# design.net
KiCad netlist of a schematic drawn in Altium Designer
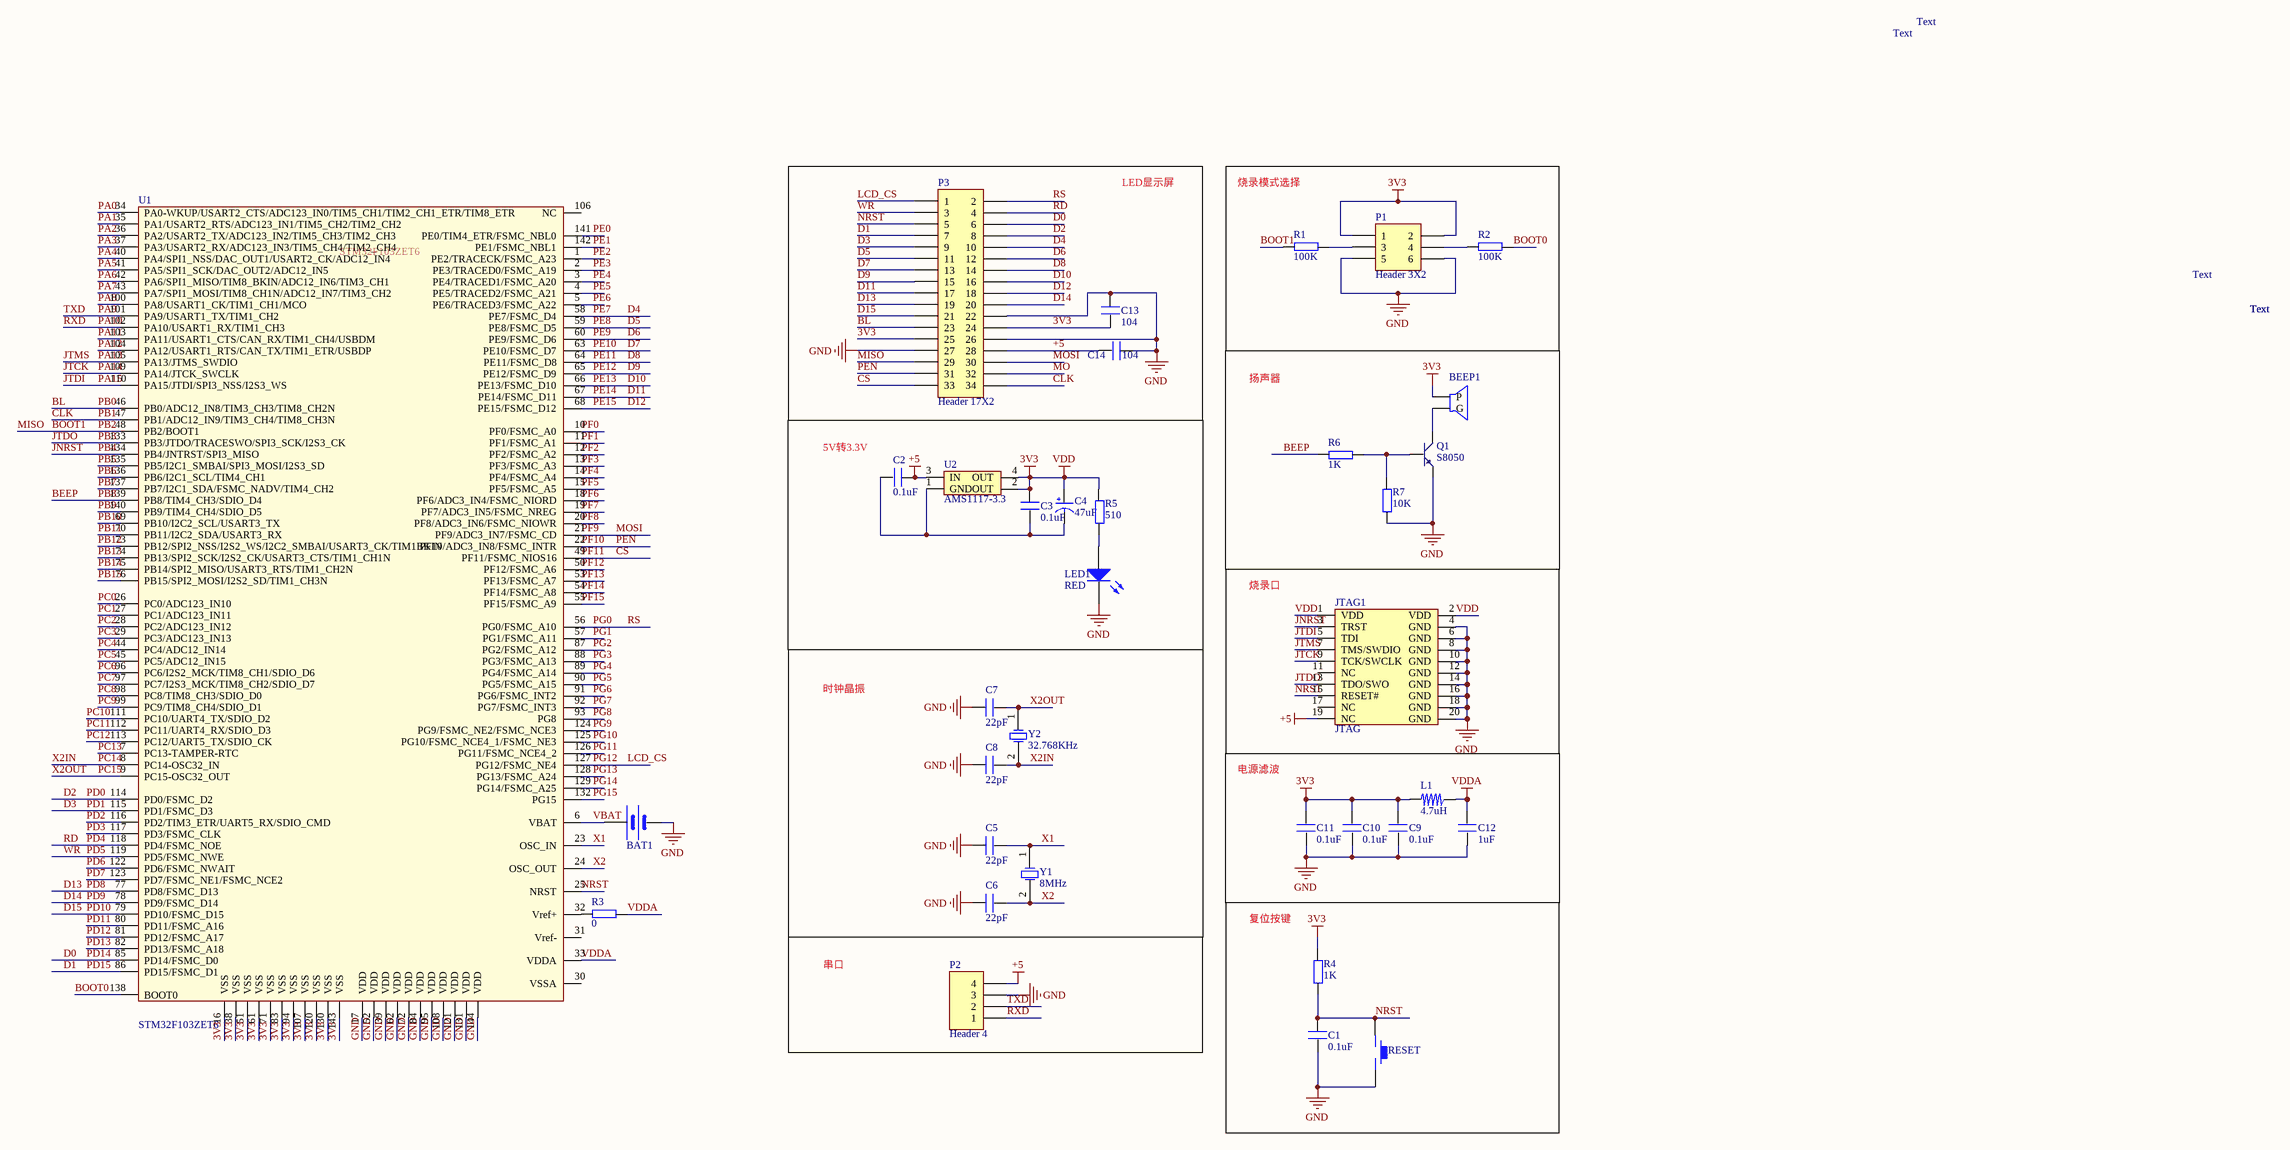
[diagram p0: 新苗.SchDoc]

(export (version "E")
  (design (tool "Eeschema 10.0.6"))
  (components
    (comp (ref "BAT1")
      (value "BATT")
      (footprint "BATM")
      (libsource (lib "WarShip V3 STM32103封装库") (part "BAT"))
    )
    (comp (ref "BEEP1")
      (value "BEEP")
      (footprint "BELL-5")
      (libsource (lib "WarShip V3 STM32103封装库") (part "BEEP"))
    )
    (comp (ref "C1")
      (value "0.1uF")
      (footprint "0603P")
      (libsource (lib "WarShip V3 STM32103封装库") (part "C"))
    )
    (comp (ref "C2")
      (value "0.1uF")
      (footprint "0603P")
      (libsource (lib "WarShip V3 STM32103封装库") (part "C"))
    )
    (comp (ref "C3")
      (value "0.1uF")
      (footprint "0603P")
      (libsource (lib "WarShip V3 STM32103封装库") (part "C"))
    )
    (comp (ref "C4")
      (value "47uF")
      (footprint "CC6.56.5")
      (libsource (lib "WarShip V3 STM32103封装库") (part "CAP"))
    )
    (comp (ref "C5") (value "22pF") (footprint "0603P") (libsource (lib "WarShip V3 STM32103封装库") (part "C")))
    (comp (ref "C6") (value "22pF") (footprint "0603P") (libsource (lib "WarShip V3 STM32103封装库") (part "C")))
    (comp (ref "C7") (value "22pF") (footprint "0603P") (libsource (lib "WarShip V3 STM32103封装库") (part "C")))
    (comp (ref "C8") (value "22pF") (footprint "0603P") (libsource (lib "WarShip V3 STM32103封装库") (part "C")))
    (comp (ref "C9")
      (value "0.1uF")
      (footprint "0603P")
      (libsource (lib "WarShip V3 STM32103封装库") (part "C"))
    )
    (comp (ref "C10")
      (value "0.1uF")
      (footprint "0603P")
      (libsource (lib "WarShip V3 STM32103封装库") (part "C"))
    )
    (comp (ref "C11")
      (value "0.1uF")
      (footprint "0603P")
      (libsource (lib "WarShip V3 STM32103封装库") (part "C"))
    )
    (comp (ref "C12") (value "1uF") (footprint "0603P") (libsource (lib "WarShip V3 STM32103封装库") (part "C")))
    (comp (ref "C13") (value "104") (footprint "0603P") (libsource (lib "WarShip V3 STM32103封装库") (part "C")))
    (comp (ref "C14") (value "104") (footprint "0603P") (libsource (lib "WarShip V3 STM32103封装库") (part "C")))
    (comp (ref "JTAG1")
      (value "JTAG")
      (footprint "JTAG_20")
      (libsource (lib "WarShip V3 STM32103封装库") (part "JTAG"))
    )
    (comp (ref "L1")
      (value "4.7uH")
      (footprint "L_SOP74")
      (libsource (lib "WarShip V3 STM32103封装库") (part "L_SOP"))
    )
    (comp (ref "LED1")
      (value "RED")
      (footprint "SMDLED")
      (description "Typical RED, GREEN, YELLOW, AMBER GaAs LED")
      (fields (field (name "PUBLISHER") "Altium Limited"))
      (libsource (lib "WarShip V3 STM32103封装库") (part "LED2"))
    )
    (comp (ref "P1")
      (value "Header 3X2")
      (footprint "HDR2X3")
      (description "Header, 3-Pin, Dual row")
      (fields (field (name "PUBLISHER") "Altium Limited"))
      (libsource (lib "Miscellaneous Connectors") (part "Header 3X2"))
    )
    (comp (ref "P2")
      (value "Header 4")
      (footprint "HDR1X4")
      (description "Header, 4-Pin")
      (fields (field (name "PUBLISHER") "Altium Limited"))
      (libsource (lib "WarShip V3 STM32103封装库") (part "Header 4"))
    )
    (comp (ref "P3")
      (value "Header 17X2")
      (footprint "HDR2X17")
      (description "Header, 17-Pin, Dual row")
      (fields (field (name "PUBLISHER") "Altium Limited"))
      (libsource (lib "Miscellaneous Connectors") (part "Header 17X2"))
    )
    (comp (ref "Q1")
      (value "S8050")
      (footprint "SOT-23R")
      (description "8050/BCW846/BCW847")
      (libsource (lib "WarShip V3 STM32103封装库") (part "NPN"))
    )
    (comp (ref "R1") (value "100K") (footprint "0603P") (libsource (lib "WarShip V3 STM32103封装库") (part "R")))
    (comp (ref "R2") (value "100K") (footprint "0603P") (libsource (lib "WarShip V3 STM32103封装库") (part "R")))
    (comp (ref "R3") (value "0") (footprint "0603P") (libsource (lib "WarShip V3 STM32103封装库") (part "R")))
    (comp (ref "R4") (value "1K") (footprint "0603P") (libsource (lib "WarShip V3 STM32103封装库") (part "R")))
    (comp (ref "R5") (value "510") (footprint "0603P") (libsource (lib "WarShip V3 STM32103封装库") (part "R")))
    (comp (ref "R6") (value "1K") (footprint "0603P") (libsource (lib "WarShip V3 STM32103封装库") (part "R")))
    (comp (ref "R7") (value "10K") (footprint "0603P") (libsource (lib "WarShip V3 STM32103封装库") (part "R")))
    (comp (ref "RESET")
      (value "KEY_M")
      (footprint "KEY_M")
      (libsource (lib "WarShip V3 STM32103封装库") (part "KEY_M"))
    )
    (comp (ref "U1")
      (value "STM32F103ZET6")
      (footprint "LQFP144")
      (libsource (lib "WarShip V3 STM32103封装库") (part "STM32F103ZET6"))
    )
    (comp (ref "U2")
      (value "AMS1117-3.3")
      (footprint "AMS1117")
      (libsource (lib "WarShip V3 STM32103封装库") (part "AMS1117"))
    )
    (comp (ref "Y1")
      (value "8MHz")
      (footprint "XTAL_US")
      (description "Crystal Oscillator")
      (fields (field (name "PUBLISHER") "Altium Limited"))
      (libsource (lib "WarShip V3 STM32103封装库") (part "XTAL"))
    )
    (comp (ref "Y2")
      (value "32.768KHz")
      (footprint "XTAL_US")
      (description "Crystal Oscillator")
      (fields (field (name "PUBLISHER") "Altium Limited"))
      (libsource (lib "WarShip V3 STM32103封装库") (part "XTAL"))
    )
  )
  (nets
    (net (code "1") (name "+5") (class "Default")
      (node (ref "C14") (pin "2") (pintype "passive"))
      (node (ref "C2") (pin "1") (pintype "passive"))
      (node (ref "JTAG1") (pin "19") (pinfunction "NC_19") (pintype "passive"))
      (node (ref "P2") (pin "4") (pinfunction "4_4") (pintype "passive"))
      (node (ref "P3") (pin "28") (pinfunction "28_28") (pintype "passive"))
      (node (ref "U2") (pin "3") (pinfunction "IN_3") (pintype "passive"))
    )
    (net (code "2") (name "/BEEP") (class "Default")
      (node (ref "R6") (pin "1") (pintype "passive"))
      (node (ref "U1") (pin "139") (pinfunction "PB8/TIM4_CH3/SDIO_D4_139") (pintype "passive"))
    )
    (net (code "3") (name "/BL") (class "Default")
      (node (ref "P3") (pin "23") (pinfunction "23_23") (pintype "passive"))
      (node (ref "U1") (pin "46") (pinfunction "PB0/ADC12_IN8/TIM3_CH3/TIM8_CH2N_46") (pintype "passive"))
    )
    (net (code "4") (name "/BOOT0") (class "Default")
      (node (ref "R2") (pin "1") (pintype "passive"))
      (node (ref "U1") (pin "138") (pinfunction "BOOT0_138") (pintype "passive"))
    )
    (net (code "5") (name "/BOOT1") (class "Default")
      (node (ref "P3") (pin "29") (pinfunction "29_29") (pintype "passive"))
      (node (ref "R1") (pin "2") (pintype "passive"))
      (node (ref "U1") (pin "48") (pinfunction "PB2/BOOT1_48") (pintype "passive"))
    )
    (net (code "6") (name "/CLK") (class "Default")
      (node (ref "P3") (pin "34") (pinfunction "34_34") (pintype "passive"))
      (node (ref "U1") (pin "47") (pinfunction "PB1/ADC12_IN9/TIM3_CH4/TIM8_CH3N_47") (pintype "passive"))
    )
    (net (code "7") (name "/CS") (class "Default")
      (node (ref "P3") (pin "33") (pinfunction "33_33") (pintype "passive"))
      (node (ref "U1") (pin "49") (pinfunction "PF11/FSMC_NIOS16_49") (pintype "passive"))
    )
    (net (code "8") (name "/D0") (class "Default")
      (node (ref "P3") (pin "6") (pinfunction "6_6") (pintype "passive"))
      (node (ref "U1") (pin "85") (pinfunction "PD14/FSMC_D0_85") (pintype "passive"))
    )
    (net (code "9") (name "/D1") (class "Default")
      (node (ref "P3") (pin "7") (pinfunction "7_7") (pintype "passive"))
      (node (ref "U1") (pin "86") (pinfunction "PD15/FSMC_D1_86") (pintype "passive"))
    )
    (net (code "10") (name "/D2") (class "Default")
      (node (ref "P3") (pin "8") (pinfunction "8_8") (pintype "passive"))
      (node (ref "U1") (pin "114") (pinfunction "PD0/FSMC_D2_114") (pintype "passive"))
    )
    (net (code "11") (name "/D3") (class "Default")
      (node (ref "P3") (pin "9") (pinfunction "9_9") (pintype "passive"))
      (node (ref "U1") (pin "115") (pinfunction "PD1/FSMC_D3_115") (pintype "passive"))
    )
    (net (code "12") (name "/D4") (class "Default")
      (node (ref "P3") (pin "10") (pinfunction "10_10") (pintype "passive"))
      (node (ref "U1") (pin "58") (pinfunction "PE7/FSMC_D4_58") (pintype "passive"))
    )
    (net (code "13") (name "/D5") (class "Default")
      (node (ref "P3") (pin "11") (pinfunction "11_11") (pintype "passive"))
      (node (ref "U1") (pin "59") (pinfunction "PE8/FSMC_D5_59") (pintype "passive"))
    )
    (net (code "14") (name "/D6") (class "Default")
      (node (ref "P3") (pin "12") (pinfunction "12_12") (pintype "passive"))
      (node (ref "U1") (pin "60") (pinfunction "PE9/FSMC_D6_60") (pintype "passive"))
    )
    (net (code "15") (name "/D7") (class "Default")
      (node (ref "P3") (pin "13") (pinfunction "13_13") (pintype "passive"))
      (node (ref "U1") (pin "63") (pinfunction "PE10/FSMC_D7_63") (pintype "passive"))
    )
    (net (code "16") (name "/D8") (class "Default")
      (node (ref "P3") (pin "14") (pinfunction "14_14") (pintype "passive"))
      (node (ref "U1") (pin "64") (pinfunction "PE11/FSMC_D8_64") (pintype "passive"))
    )
    (net (code "17") (name "/D9") (class "Default")
      (node (ref "P3") (pin "15") (pinfunction "15_15") (pintype "passive"))
      (node (ref "U1") (pin "65") (pinfunction "PE12/FSMC_D9_65") (pintype "passive"))
    )
    (net (code "18") (name "/D10") (class "Default")
      (node (ref "P3") (pin "16") (pinfunction "16_16") (pintype "passive"))
      (node (ref "U1") (pin "66") (pinfunction "PE13/FSMC_D10_66") (pintype "passive"))
    )
    (net (code "19") (name "/D11") (class "Default")
      (node (ref "P3") (pin "17") (pinfunction "17_17") (pintype "passive"))
      (node (ref "U1") (pin "67") (pinfunction "PE14/FSMC_D11_67") (pintype "passive"))
    )
    (net (code "20") (name "/D12") (class "Default")
      (node (ref "P3") (pin "18") (pinfunction "18_18") (pintype "passive"))
      (node (ref "U1") (pin "68") (pinfunction "PE15/FSMC_D12_68") (pintype "passive"))
    )
    (net (code "21") (name "/D13") (class "Default")
      (node (ref "P3") (pin "19") (pinfunction "19_19") (pintype "passive"))
      (node (ref "U1") (pin "77") (pinfunction "PD8/FSMC_D13_77") (pintype "passive"))
    )
    (net (code "22") (name "/D14") (class "Default")
      (node (ref "P3") (pin "20") (pinfunction "20_20") (pintype "passive"))
      (node (ref "U1") (pin "78") (pinfunction "PD9/FSMC_D14_78") (pintype "passive"))
    )
    (net (code "23") (name "/D15") (class "Default")
      (node (ref "P3") (pin "21") (pinfunction "21_21") (pintype "passive"))
      (node (ref "U1") (pin "79") (pinfunction "PD10/FSMC_D15_79") (pintype "passive"))
    )
    (net (code "24") (name "/JNRST") (class "Default")
      (node (ref "JTAG1") (pin "3") (pinfunction "TRST_3") (pintype "passive"))
      (node (ref "U1") (pin "134") (pinfunction "PB4/JNTRST/SPI3_MISO_134") (pintype "passive"))
    )
    (net (code "25") (name "/JTCK") (class "Default")
      (node (ref "JTAG1") (pin "9") (pinfunction "TCK/SWCLK_9") (pintype "passive"))
      (node (ref "U1") (pin "109") (pinfunction "PA14/JTCK_SWCLK_109") (pintype "passive"))
    )
    (net (code "26") (name "/JTDI") (class "Default")
      (node (ref "JTAG1") (pin "5") (pinfunction "TDI_5") (pintype "passive"))
      (node (ref "U1") (pin "110") (pinfunction "PA15/JTDI/SPI3_NSS/I2S3_WS_110") (pintype "passive"))
    )
    (net (code "27") (name "/JTDO") (class "Default")
      (node (ref "JTAG1") (pin "13") (pinfunction "TDO/SWO_13") (pintype "passive"))
      (node (ref "U1") (pin "133") (pinfunction "PB3/JTDO/TRACESWO/SPI3_SCK/I2S3_CK_133") (pintype "passive"))
    )
    (net (code "28") (name "/JTMS") (class "Default")
      (node (ref "JTAG1") (pin "7") (pinfunction "TMS/SWDIO_7") (pintype "passive"))
      (node (ref "U1") (pin "105") (pinfunction "PA13/JTMS_SWDIO_105") (pintype "passive"))
    )
    (net (code "29") (name "/LCD_CS") (class "Default")
      (node (ref "P3") (pin "1") (pinfunction "1_1") (pintype "passive"))
      (node (ref "U1") (pin "127") (pinfunction "PG12/FSMC_NE4_127") (pintype "passive"))
    )
    (net (code "30") (name "/MO") (class "Default")
      (node (ref "P3") (pin "32") (pinfunction "32_32") (pintype "passive"))
    )
    (net (code "31") (name "/MOSI") (class "Default")
      (node (ref "P3") (pin "30") (pinfunction "30_30") (pintype "passive"))
      (node (ref "U1") (pin "21") (pinfunction "PF9/ADC3_IN7/FSMC_CD_21") (pintype "passive"))
    )
    (net (code "32") (name "/NRST") (class "Default")
      (node (ref "C1") (pin "2") (pintype "passive"))
      (node (ref "JTAG1") (pin "15") (pinfunction "RESET#_15") (pintype "passive"))
      (node (ref "P3") (pin "5") (pinfunction "5_5") (pintype "passive"))
      (node (ref "R4") (pin "1") (pintype "passive"))
      (node (ref "RESET") (pin "1") (pinfunction "1_1") (pintype "passive"))
      (node (ref "U1") (pin "25") (pinfunction "NRST_25") (pintype "passive"))
    )
    (net (code "33") (name "/PA0") (class "Default")
      (node (ref "U1") (pin "34") (pinfunction "PA0-WKUP/USART2_CTS/ADC123_IN0/TIM5_CH1/TIM2_CH1_ETR/TIM8_ETR_34") (pintype "passive"))
    )
    (net (code "34") (name "/PA1") (class "Default")
      (node (ref "U1") (pin "35") (pinfunction "PA1/USART2_RTS/ADC123_IN1/TIM5_CH2/TIM2_CH2_35") (pintype "passive"))
    )
    (net (code "35") (name "/PA2") (class "Default")
      (node (ref "U1") (pin "36") (pinfunction "PA2/USART2_TX/ADC123_IN2/TIM5_CH3/TIM2_CH3_36") (pintype "passive"))
    )
    (net (code "36") (name "/PA3") (class "Default")
      (node (ref "U1") (pin "37") (pinfunction "PA3/USART2_RX/ADC123_IN3/TIM5_CH4/TIM2_CH4_37") (pintype "passive"))
    )
    (net (code "37") (name "/PA4") (class "Default")
      (node (ref "U1") (pin "40") (pinfunction "PA4/SPI1_NSS/DAC_OUT1/USART2_CK/ADC12_IN4_40") (pintype "passive"))
    )
    (net (code "38") (name "/PA5") (class "Default")
      (node (ref "U1") (pin "41") (pinfunction "PA5/SPI1_SCK/DAC_OUT2/ADC12_IN5_41") (pintype "passive"))
    )
    (net (code "39") (name "/PA6") (class "Default")
      (node (ref "U1") (pin "42") (pinfunction "PA6/SPI1_MISO/TIM8_BKIN/ADC12_IN6/TIM3_CH1_42") (pintype "passive"))
    )
    (net (code "40") (name "/PA7") (class "Default")
      (node (ref "U1") (pin "43") (pinfunction "PA7/SPI1_MOSI/TIM8_CH1N/ADC12_IN7/TIM3_CH2_43") (pintype "passive"))
    )
    (net (code "41") (name "/PA8") (class "Default")
      (node (ref "U1") (pin "100") (pinfunction "PA8/USART1_CK/TIM1_CH1/MCO_100") (pintype "passive"))
    )
    (net (code "42") (name "/PA9") (class "Default")
      (node (ref "P2") (pin "2") (pinfunction "2_2") (pintype "passive"))
      (node (ref "U1") (pin "101") (pinfunction "PA9/USART1_TX/TIM1_CH2_101") (pintype "passive"))
    )
    (net (code "43") (name "/PA10") (class "Default")
      (node (ref "P2") (pin "1") (pinfunction "1_1") (pintype "passive"))
      (node (ref "U1") (pin "102") (pinfunction "PA10/USART1_RX/TIM1_CH3_102") (pintype "passive"))
    )
    (net (code "44") (name "/PA11") (class "Default")
      (node (ref "U1") (pin "103") (pinfunction "PA11/USART1_CTS/CAN_RX/TIM1_CH4/USBDM_103") (pintype "passive"))
    )
    (net (code "45") (name "/PA12") (class "Default")
      (node (ref "U1") (pin "104") (pinfunction "PA12/USART1_RTS/CAN_TX/TIM1_ETR/USBDP_104") (pintype "passive"))
    )
    (net (code "46") (name "/PB5") (class "Default")
      (node (ref "U1") (pin "135") (pinfunction "PB5/I2C1_SMBAI/SPI3_MOSI/I2S3_SD_135") (pintype "passive"))
    )
    (net (code "47") (name "/PB6") (class "Default")
      (node (ref "U1") (pin "136") (pinfunction "PB6/I2C1_SCL/TIM4_CH1_136") (pintype "passive"))
    )
    (net (code "48") (name "/PB7") (class "Default")
      (node (ref "U1") (pin "137") (pinfunction "PB7/I2C1_SDA/FSMC_NADV/TIM4_CH2_137") (pintype "passive"))
    )
    (net (code "49") (name "/PB9") (class "Default")
      (node (ref "U1") (pin "140") (pinfunction "PB9/TIM4_CH4/SDIO_D5_140") (pintype "passive"))
    )
    (net (code "50") (name "/PB10") (class "Default")
      (node (ref "U1") (pin "69") (pinfunction "PB10/I2C2_SCL/USART3_TX_69") (pintype "passive"))
    )
    (net (code "51") (name "/PB11") (class "Default")
      (node (ref "U1") (pin "70") (pinfunction "PB11/I2C2_SDA/USART3_RX_70") (pintype "passive"))
    )
    (net (code "52") (name "/PB12") (class "Default")
      (node (ref "U1") (pin "73") (pinfunction "PB12/SPI2_NSS/I2S2_WS/I2C2_SMBAI/USART3_CK/TIM1BKIN_73") (pintype "passive"))
    )
    (net (code "53") (name "/PB13") (class "Default")
      (node (ref "U1") (pin "74") (pinfunction "PB13/SPI2_SCK/I2S2_CK/USART3_CTS/TIM1_CH1N_74") (pintype "passive"))
    )
    (net (code "54") (name "/PB14") (class "Default")
      (node (ref "U1") (pin "75") (pinfunction "PB14/SPI2_MISO/USART3_RTS/TIM1_CH2N_75") (pintype "passive"))
    )
    (net (code "55") (name "/PB15") (class "Default")
      (node (ref "U1") (pin "76") (pinfunction "PB15/SPI2_MOSI/I2S2_SD/TIM1_CH3N_76") (pintype "passive"))
    )
    (net (code "56") (name "/PC0") (class "Default")
      (node (ref "U1") (pin "26") (pinfunction "PC0/ADC123_IN10_26") (pintype "passive"))
    )
    (net (code "57") (name "/PC1") (class "Default")
      (node (ref "U1") (pin "27") (pinfunction "PC1/ADC123_IN11_27") (pintype "passive"))
    )
    (net (code "58") (name "/PC2") (class "Default")
      (node (ref "U1") (pin "28") (pinfunction "PC2/ADC123_IN12_28") (pintype "passive"))
    )
    (net (code "59") (name "/PC3") (class "Default")
      (node (ref "U1") (pin "29") (pinfunction "PC3/ADC123_IN13_29") (pintype "passive"))
    )
    (net (code "60") (name "/PC4") (class "Default")
      (node (ref "U1") (pin "44") (pinfunction "PC4/ADC12_IN14_44") (pintype "passive"))
    )
    (net (code "61") (name "/PC5") (class "Default")
      (node (ref "U1") (pin "45") (pinfunction "PC5/ADC12_IN15_45") (pintype "passive"))
    )
    (net (code "62") (name "/PC6") (class "Default")
      (node (ref "U1") (pin "96") (pinfunction "PC6/I2S2_MCK/TIM8_CH1/SDIO_D6_96") (pintype "passive"))
    )
    (net (code "63") (name "/PC7") (class "Default")
      (node (ref "U1") (pin "97") (pinfunction "PC7/I2S3_MCK/TIM8_CH2/SDIO_D7_97") (pintype "passive"))
    )
    (net (code "64") (name "/PC8") (class "Default")
      (node (ref "U1") (pin "98") (pinfunction "PC8/TIM8_CH3/SDIO_D0_98") (pintype "passive"))
    )
    (net (code "65") (name "/PC9") (class "Default")
      (node (ref "U1") (pin "99") (pinfunction "PC9/TIM8_CH4/SDIO_D1_99") (pintype "passive"))
    )
    (net (code "66") (name "/PC10") (class "Default")
      (node (ref "U1") (pin "111") (pinfunction "PC10/UART4_TX/SDIO_D2_111") (pintype "passive"))
    )
    (net (code "67") (name "/PC11") (class "Default")
      (node (ref "U1") (pin "112") (pinfunction "PC11/UART4_RX/SDIO_D3_112") (pintype "passive"))
    )
    (net (code "68") (name "/PC12") (class "Default")
      (node (ref "U1") (pin "113") (pinfunction "PC12/UART5_TX/SDIO_CK_113") (pintype "passive"))
    )
    (net (code "69") (name "/PC13") (class "Default")
      (node (ref "U1") (pin "7") (pinfunction "PC13-TAMPER-RTC_7") (pintype "passive"))
    )
    (net (code "70") (name "/PC14") (class "Default")
      (node (ref "C8") (pin "2") (pintype "passive"))
      (node (ref "U1") (pin "8") (pinfunction "PC14-OSC32_IN_8") (pintype "passive"))
      (node (ref "Y2") (pin "2") (pinfunction "OSC2_2") (pintype "passive"))
    )
    (net (code "71") (name "/PC15") (class "Default")
      (node (ref "C7") (pin "2") (pintype "passive"))
      (node (ref "U1") (pin "9") (pinfunction "PC15-OSC32_OUT_9") (pintype "passive"))
      (node (ref "Y2") (pin "1") (pinfunction "OSC1_1") (pintype "passive"))
    )
    (net (code "72") (name "/PD2") (class "Default")
      (node (ref "U1") (pin "116") (pinfunction "PD2/TIM3_ETR/UART5_RX/SDIO_CMD_116") (pintype "passive"))
    )
    (net (code "73") (name "/PD3") (class "Default")
      (node (ref "U1") (pin "117") (pinfunction "PD3/FSMC_CLK_117") (pintype "passive"))
    )
    (net (code "74") (name "/PD4") (class "Default")
      (node (ref "P3") (pin "4") (pinfunction "4_4") (pintype "passive"))
      (node (ref "U1") (pin "118") (pinfunction "PD4/FSMC_NOE_118") (pintype "passive"))
    )
    (net (code "75") (name "/PD5") (class "Default")
      (node (ref "P3") (pin "3") (pinfunction "3_3") (pintype "passive"))
      (node (ref "U1") (pin "119") (pinfunction "PD5/FSMC_NWE_119") (pintype "passive"))
    )
    (net (code "76") (name "/PD6") (class "Default")
      (node (ref "U1") (pin "122") (pinfunction "PD6/FSMC_NWAIT_122") (pintype "passive"))
    )
    (net (code "77") (name "/PD7") (class "Default")
      (node (ref "U1") (pin "123") (pinfunction "PD7/FSMC_NE1/FSMC_NCE2_123") (pintype "passive"))
    )
    (net (code "78") (name "/PD11") (class "Default")
      (node (ref "U1") (pin "80") (pinfunction "PD11/FSMC_A16_80") (pintype "passive"))
    )
    (net (code "79") (name "/PD12") (class "Default")
      (node (ref "U1") (pin "81") (pinfunction "PD12/FSMC_A17_81") (pintype "passive"))
    )
    (net (code "80") (name "/PD13") (class "Default")
      (node (ref "U1") (pin "82") (pinfunction "PD13/FSMC_A18_82") (pintype "passive"))
    )
    (net (code "81") (name "/PE0") (class "Default")
      (node (ref "U1") (pin "141") (pinfunction "PE0/TIM4_ETR/FSMC_NBL0_141") (pintype "passive"))
    )
    (net (code "82") (name "/PE1") (class "Default")
      (node (ref "U1") (pin "142") (pinfunction "PE1/FSMC_NBL1_142") (pintype "passive"))
    )
    (net (code "83") (name "/PE2") (class "Default")
      (node (ref "U1") (pin "1") (pinfunction "PE2/TRACECK/FSMC_A23_1") (pintype "passive"))
    )
    (net (code "84") (name "/PE3") (class "Default")
      (node (ref "U1") (pin "2") (pinfunction "PE3/TRACED0/FSMC_A19_2") (pintype "passive"))
    )
    (net (code "85") (name "/PE4") (class "Default")
      (node (ref "U1") (pin "3") (pinfunction "PE4/TRACED1/FSMC_A20_3") (pintype "passive"))
    )
    (net (code "86") (name "/PE5") (class "Default")
      (node (ref "U1") (pin "4") (pinfunction "PE5/TRACED2/FSMC_A21_4") (pintype "passive"))
    )
    (net (code "87") (name "/PE6") (class "Default")
      (node (ref "U1") (pin "5") (pinfunction "PE6/TRACED3/FSMC_A22_5") (pintype "passive"))
    )
    (net (code "88") (name "/PEN") (class "Default")
      (node (ref "P3") (pin "31") (pinfunction "31_31") (pintype "passive"))
      (node (ref "U1") (pin "22") (pinfunction "PF10/ADC3_IN8/FSMC_INTR_22") (pintype "passive"))
    )
    (net (code "89") (name "/PF0") (class "Default")
      (node (ref "U1") (pin "10") (pinfunction "PF0/FSMC_A0_10") (pintype "passive"))
    )
    (net (code "90") (name "/PF1") (class "Default")
      (node (ref "U1") (pin "11") (pinfunction "PF1/FSMC_A1_11") (pintype "passive"))
    )
    (net (code "91") (name "/PF2") (class "Default")
      (node (ref "U1") (pin "12") (pinfunction "PF2/FSMC_A2_12") (pintype "passive"))
    )
    (net (code "92") (name "/PF3") (class "Default")
      (node (ref "U1") (pin "13") (pinfunction "PF3/FSMC_A3_13") (pintype "passive"))
    )
    (net (code "93") (name "/PF4") (class "Default")
      (node (ref "U1") (pin "14") (pinfunction "PF4/FSMC_A4_14") (pintype "passive"))
    )
    (net (code "94") (name "/PF5") (class "Default")
      (node (ref "U1") (pin "15") (pinfunction "PF5/FSMC_A5_15") (pintype "passive"))
    )
    (net (code "95") (name "/PF6") (class "Default")
      (node (ref "U1") (pin "18") (pinfunction "PF6/ADC3_IN4/FSMC_NIORD_18") (pintype "passive"))
    )
    (net (code "96") (name "/PF7") (class "Default")
      (node (ref "U1") (pin "19") (pinfunction "PF7/ADC3_IN5/FSMC_NREG_19") (pintype "passive"))
    )
    (net (code "97") (name "/PF8") (class "Default")
      (node (ref "U1") (pin "20") (pinfunction "PF8/ADC3_IN6/FSMC_NIOWR_20") (pintype "passive"))
    )
    (net (code "98") (name "/PF12") (class "Default")
      (node (ref "U1") (pin "50") (pinfunction "PF12/FSMC_A6_50") (pintype "passive"))
    )
    (net (code "99") (name "/PF13") (class "Default")
      (node (ref "U1") (pin "53") (pinfunction "PF13/FSMC_A7_53") (pintype "passive"))
    )
    (net (code "100") (name "/PF14") (class "Default")
      (node (ref "U1") (pin "54") (pinfunction "PF14/FSMC_A8_54") (pintype "passive"))
    )
    (net (code "101") (name "/PF15") (class "Default")
      (node (ref "U1") (pin "55") (pinfunction "PF15/FSMC_A9_55") (pintype "passive"))
    )
    (net (code "102") (name "/PG0") (class "Default")
      (node (ref "P3") (pin "2") (pinfunction "2_2") (pintype "passive"))
      (node (ref "U1") (pin "56") (pinfunction "PG0/FSMC_A10_56") (pintype "passive"))
    )
    (net (code "103") (name "/PG1") (class "Default")
      (node (ref "U1") (pin "57") (pinfunction "PG1/FSMC_A11_57") (pintype "passive"))
    )
    (net (code "104") (name "/PG2") (class "Default")
      (node (ref "U1") (pin "87") (pinfunction "PG2/FSMC_A12_87") (pintype "passive"))
    )
    (net (code "105") (name "/PG3") (class "Default")
      (node (ref "U1") (pin "88") (pinfunction "PG3/FSMC_A13_88") (pintype "passive"))
    )
    (net (code "106") (name "/PG4") (class "Default")
      (node (ref "U1") (pin "89") (pinfunction "PG4/FSMC_A14_89") (pintype "passive"))
    )
    (net (code "107") (name "/PG5") (class "Default")
      (node (ref "U1") (pin "90") (pinfunction "PG5/FSMC_A15_90") (pintype "passive"))
    )
    (net (code "108") (name "/PG6") (class "Default")
      (node (ref "U1") (pin "91") (pinfunction "PG6/FSMC_INT2_91") (pintype "passive"))
    )
    (net (code "109") (name "/PG7") (class "Default")
      (node (ref "U1") (pin "92") (pinfunction "PG7/FSMC_INT3_92") (pintype "passive"))
    )
    (net (code "110") (name "/PG8") (class "Default")
      (node (ref "U1") (pin "93") (pinfunction "PG8_93") (pintype "passive"))
    )
    (net (code "111") (name "/PG9") (class "Default")
      (node (ref "U1") (pin "124") (pinfunction "PG9/FSMC_NE2/FSMC_NCE3_124") (pintype "passive"))
    )
    (net (code "112") (name "/PG10") (class "Default")
      (node (ref "U1") (pin "125") (pinfunction "PG10/FSMC_NCE4_1/FSMC_NE3_125") (pintype "passive"))
    )
    (net (code "113") (name "/PG11") (class "Default")
      (node (ref "U1") (pin "126") (pinfunction "PG11/FSMC_NCE4_2_126") (pintype "passive"))
    )
    (net (code "114") (name "/PG13") (class "Default")
      (node (ref "U1") (pin "128") (pinfunction "PG13/FSMC_A24_128") (pintype "passive"))
    )
    (net (code "115") (name "/PG14") (class "Default")
      (node (ref "U1") (pin "129") (pinfunction "PG14/FSMC_A25_129") (pintype "passive"))
    )
    (net (code "116") (name "/PG15") (class "Default")
      (node (ref "U1") (pin "132") (pinfunction "PG15_132") (pintype "passive"))
    )
    (net (code "117") (name "/VBAT") (class "Default")
      (node (ref "BAT1") (pin "1") (pinfunction "VCC_1") (pintype "passive"))
      (node (ref "U1") (pin "6") (pinfunction "VBAT_6") (pintype "passive"))
    )
    (net (code "118") (name "/X1") (class "Default")
      (node (ref "C5") (pin "2") (pintype "passive"))
      (node (ref "U1") (pin "23") (pinfunction "OSC_IN_23") (pintype "passive"))
      (node (ref "Y1") (pin "1") (pinfunction "OSC1_1") (pintype "passive"))
    )
    (net (code "119") (name "/X2") (class "Default")
      (node (ref "C6") (pin "2") (pintype "passive"))
      (node (ref "U1") (pin "24") (pinfunction "OSC_OUT_24") (pintype "passive"))
      (node (ref "Y1") (pin "2") (pinfunction "OSC2_2") (pintype "passive"))
    )
    (net (code "120") (name "3V3") (class "Default")
      (node (ref "BEEP1") (pin "1") (pinfunction "P_1") (pintype "passive"))
      (node (ref "C10") (pin "2") (pintype "passive"))
      (node (ref "C11") (pin "2") (pintype "passive"))
      (node (ref "C13") (pin "1") (pintype "passive"))
      (node (ref "C3") (pin "2") (pintype "passive"))
      (node (ref "C4") (pin "1") (pinfunction "VCC_1") (pintype "passive"))
      (node (ref "C9") (pin "2") (pintype "passive"))
      (node (ref "JTAG1") (pin "1") (pinfunction "VDD_1") (pintype "passive"))
      (node (ref "JTAG1") (pin "2") (pinfunction "VDD_2") (pintype "passive"))
      (node (ref "L1") (pin "2") (pinfunction "2_2") (pintype "passive"))
      (node (ref "P1") (pin "1") (pinfunction "1_1") (pintype "passive"))
      (node (ref "P1") (pin "2") (pinfunction "2_2") (pintype "passive"))
      (node (ref "P3") (pin "24") (pinfunction "24_24") (pintype "passive"))
      (node (ref "P3") (pin "25") (pinfunction "25_25") (pintype "passive"))
      (node (ref "R4") (pin "2") (pintype "passive"))
      (node (ref "R5") (pin "2") (pintype "passive"))
      (node (ref "U1") (pin "107") (pinfunction "VSS_107") (pintype "passive"))
      (node (ref "U1") (pin "120") (pinfunction "VSS_120") (pintype "passive"))
      (node (ref "U1") (pin "130") (pinfunction "VSS_130") (pintype "passive"))
      (node (ref "U1") (pin "143") (pinfunction "VSS_143") (pintype "passive"))
      (node (ref "U1") (pin "16") (pinfunction "VSS_16") (pintype "passive"))
      (node (ref "U1") (pin "38") (pinfunction "VSS_38") (pintype "passive"))
      (node (ref "U1") (pin "51") (pinfunction "VSS_51") (pintype "passive"))
      (node (ref "U1") (pin "61") (pinfunction "VSS_61") (pintype "passive"))
      (node (ref "U1") (pin "71") (pinfunction "VSS_71") (pintype "passive"))
      (node (ref "U1") (pin "83") (pinfunction "VSS_83") (pintype "passive"))
      (node (ref "U1") (pin "94") (pinfunction "VSS_94") (pintype "passive"))
      (node (ref "U2") (pin "2") (pinfunction "OUT_2") (pintype "passive"))
      (node (ref "U2") (pin "4") (pinfunction "OUT_4") (pintype "passive"))
    )
    (net (code "121") (name "GND") (class "Default")
      (node (ref "BAT1") (pin "2") (pinfunction "GND_2") (pintype "passive"))
      (node (ref "C1") (pin "1") (pintype "passive"))
      (node (ref "C10") (pin "1") (pintype "passive"))
      (node (ref "C11") (pin "1") (pintype "passive"))
      (node (ref "C12") (pin "1") (pintype "passive"))
      (node (ref "C13") (pin "2") (pintype "passive"))
      (node (ref "C14") (pin "1") (pintype "passive"))
      (node (ref "C5") (pin "1") (pintype "passive"))
      (node (ref "C6") (pin "1") (pintype "passive"))
      (node (ref "C7") (pin "1") (pintype "passive"))
      (node (ref "C8") (pin "1") (pintype "passive"))
      (node (ref "C9") (pin "1") (pintype "passive"))
      (node (ref "JTAG1") (pin "10") (pinfunction "GND_10") (pintype "passive"))
      (node (ref "JTAG1") (pin "12") (pinfunction "GND_12") (pintype "passive"))
      (node (ref "JTAG1") (pin "14") (pinfunction "GND_14") (pintype "passive"))
      (node (ref "JTAG1") (pin "16") (pinfunction "GND_16") (pintype "passive"))
      (node (ref "JTAG1") (pin "18") (pinfunction "GND_18") (pintype "passive"))
      (node (ref "JTAG1") (pin "20") (pinfunction "GND_20") (pintype "passive"))
      (node (ref "JTAG1") (pin "4") (pinfunction "GND_4") (pintype "passive"))
      (node (ref "JTAG1") (pin "6") (pinfunction "GND_6") (pintype "passive"))
      (node (ref "JTAG1") (pin "8") (pinfunction "GND_8") (pintype "passive"))
      (node (ref "LED1") (pin "2") (pinfunction "K_2") (pintype "passive"))
      (node (ref "P1") (pin "5") (pinfunction "5_5") (pintype "passive"))
      (node (ref "P1") (pin "6") (pinfunction "6_6") (pintype "passive"))
      (node (ref "P2") (pin "3") (pinfunction "3_3") (pintype "passive"))
      (node (ref "P3") (pin "22") (pinfunction "22_22") (pintype "passive"))
      (node (ref "P3") (pin "26") (pinfunction "26_26") (pintype "passive"))
      (node (ref "P3") (pin "27") (pinfunction "27_27") (pintype "passive"))
      (node (ref "Q1") (pin "1") (pinfunction "E_1") (pintype "passive"))
      (node (ref "R7") (pin "1") (pintype "passive"))
      (node (ref "RESET") (pin "2") (pinfunction "2_2") (pintype "passive"))
      (node (ref "U1") (pin "108") (pinfunction "VDD_108") (pintype "passive"))
      (node (ref "U1") (pin "121") (pinfunction "VDD_121") (pintype "passive"))
      (node (ref "U1") (pin "131") (pinfunction "VDD_131") (pintype "passive"))
      (node (ref "U1") (pin "144") (pinfunction "VDD_144") (pintype "passive"))
      (node (ref "U1") (pin "17") (pinfunction "VDD_17") (pintype "passive"))
      (node (ref "U1") (pin "39") (pinfunction "VDD_39") (pintype "passive"))
      (node (ref "U1") (pin "52") (pinfunction "VDD_52") (pintype "passive"))
      (node (ref "U1") (pin "62") (pinfunction "VDD_62") (pintype "passive"))
      (node (ref "U1") (pin "72") (pinfunction "VDD_72") (pintype "passive"))
      (node (ref "U1") (pin "84") (pinfunction "VDD_84") (pintype "passive"))
      (node (ref "U1") (pin "95") (pinfunction "VDD_95") (pintype "passive"))
    )
    (net (code "122") (name "Net-(BEEP1-G)") (class "Default")
      (node (ref "BEEP1") (pin "2") (pinfunction "G_2") (pintype "passive"))
      (node (ref "Q1") (pin "3") (pinfunction "C_3") (pintype "passive"))
    )
    (net (code "123") (name "Net-(C4-GND)") (class "Default")
      (node (ref "C2") (pin "2") (pintype "passive"))
      (node (ref "C3") (pin "1") (pintype "passive"))
      (node (ref "C4") (pin "2") (pinfunction "GND_2") (pintype "passive"))
      (node (ref "U2") (pin "1") (pinfunction "GND_1") (pintype "passive"))
    )
    (net (code "124") (name "Net-(LED1-A)") (class "Default")
      (node (ref "LED1") (pin "1") (pinfunction "A_1") (pintype "passive"))
      (node (ref "R5") (pin "1") (pintype "passive"))
    )
    (net (code "125") (name "Net-(P1-Pad3)") (class "Default")
      (node (ref "P1") (pin "3") (pinfunction "3_3") (pintype "passive"))
      (node (ref "R1") (pin "1") (pintype "passive"))
    )
    (net (code "126") (name "Net-(P1-Pad4)") (class "Default")
      (node (ref "P1") (pin "4") (pinfunction "4_4") (pintype "passive"))
      (node (ref "R2") (pin "2") (pintype "passive"))
    )
    (net (code "127") (name "Net-(Q1-B)") (class "Default")
      (node (ref "Q1") (pin "2") (pinfunction "B_2") (pintype "passive"))
      (node (ref "R6") (pin "2") (pintype "passive"))
      (node (ref "R7") (pin "2") (pintype "passive"))
    )
    (net (code "128") (name "Net-(U1-Vref+)") (class "Default")
      (node (ref "R3") (pin "2") (pintype "passive"))
      (node (ref "U1") (pin "32") (pinfunction "Vref+_32") (pintype "passive"))
    )
    (net (code "129") (name "VDDA") (class "Default")
      (node (ref "C12") (pin "2") (pintype "passive"))
      (node (ref "L1") (pin "1") (pinfunction "1_1") (pintype "passive"))
      (node (ref "R3") (pin "1") (pintype "passive"))
      (node (ref "U1") (pin "33") (pinfunction "VDDA_33") (pintype "passive"))
    )
    (net (code "130") (name "unconnected-(JTAG1-NC-Pad11)") (class "Default")
      (node (ref "JTAG1") (pin "11") (pinfunction "NC_11") (pintype "passive"))
    )
    (net (code "131") (name "unconnected-(JTAG1-NC-Pad17)") (class "Default")
      (node (ref "JTAG1") (pin "17") (pinfunction "NC_17") (pintype "passive"))
    )
    (net (code "132") (name "unconnected-(U1-NC-Pad106)") (class "Default")
      (node (ref "U1") (pin "106") (pinfunction "NC_106") (pintype "passive"))
    )
    (net (code "133") (name "unconnected-(U1-VSSA-Pad30)") (class "Default")
      (node (ref "U1") (pin "30") (pinfunction "VSSA_30") (pintype "passive"))
    )
    (net (code "134") (name "unconnected-(U1-Vref--Pad31)") (class "Default")
      (node (ref "U1") (pin "31") (pinfunction "Vref-_31") (pintype "passive"))
    )
  )
)
